# stromplatine.net
KiCad netlist of a schematic drawn in EAGLE
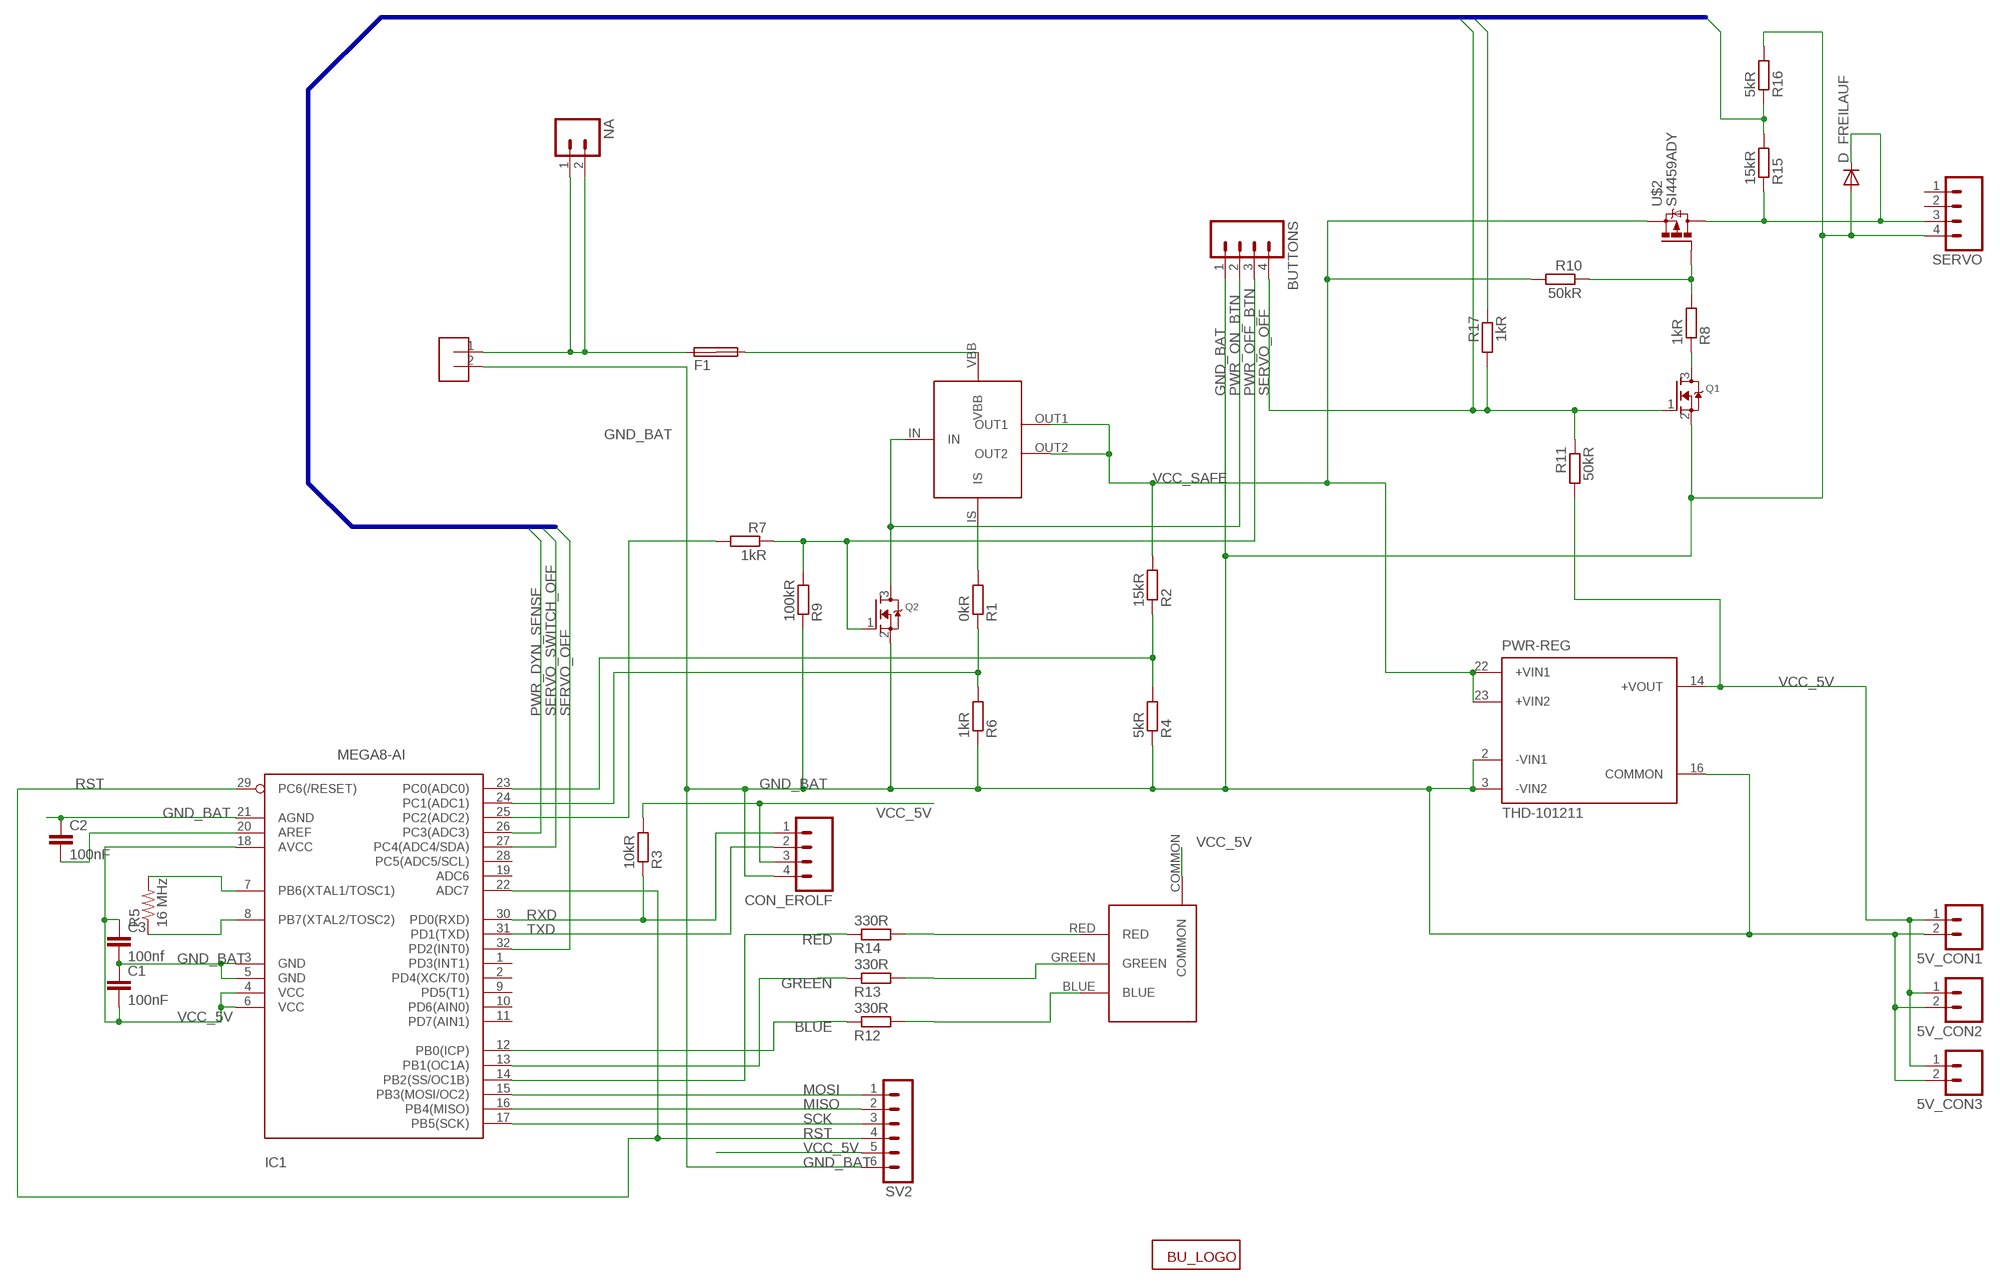
[diagram p0: schematic, sheet 1]

(export (version "E")
  (design (tool "Eeschema 10.0.6"))
  (components
    (comp (ref "5V_CON1")
      (value "M02")
      (footprint "eagle-import:02P")
      (libsource (lib "eagle-import") (part "M02"))
    )
    (comp (ref "5V_CON2")
      (value "M02")
      (footprint "eagle-import:02P")
      (libsource (lib "eagle-import") (part "M02"))
    )
    (comp (ref "5V_CON3")
      (value "M02")
      (footprint "eagle-import:02P")
      (libsource (lib "eagle-import") (part "M02"))
    )
    (comp (ref "BUTTONS")
      (value "M04")
      (footprint "eagle-import:04P")
      (fields (field (name "OC_FARNELL") "unknown") (field (name "OC_NEWARK") "unknown"))
      (libsource (lib "eagle-import") (part "M04"))
    )
    (comp (ref "C1")
      (value "100nF")
      (footprint "eagle-import:C0805")
      (libsource (lib "eagle-import") (part "C-EUC0805"))
    )
    (comp (ref "C2")
      (value "100nF")
      (footprint "eagle-import:C0805")
      (libsource (lib "eagle-import") (part "C-EUC0805"))
    )
    (comp (ref "C3")
      (value "100nf")
      (footprint "eagle-import:C0805")
      (libsource (lib "eagle-import") (part "C-EUC0805"))
    )
    (comp (ref "CON_BAT")
      (value "STROMSTECKER")
      (footprint "eagle-import:STROMSTECKER")
      (libsource (lib "eagle-import") (part "STROMSTECKER"))
    )
    (comp (ref "CON_EROLF")
      (value "M04")
      (footprint "eagle-import:04P")
      (fields (field (name "OC_FARNELL") "unknown") (field (name "OC_NEWARK") "unknown"))
      (libsource (lib "eagle-import") (part "M04"))
    )
    (comp (ref "D_FREILAUF")
      (value "DIODE-DO-214AC")
      (footprint "eagle-import:DO-214AC")
      (libsource (lib "eagle-import") (part "DIODE-DO-214AC"))
    )
    (comp (ref "F1")
      (value "SHK20Q")
      (footprint "eagle-import:SHK20Q")
      (libsource (lib "eagle-import") (part "SHK20Q"))
    )
    (comp (ref "IC1")
      (value "MEGA8-AI")
      (footprint "eagle-import:TQFP32-08")
      (libsource (lib "eagle-import") (part "MEGA8-AI"))
    )
    (comp (ref "NA")
      (value "M02")
      (footprint "eagle-import:02P")
      (fields (field (name "OC_FARNELL") "unknown") (field (name "OC_NEWARK") "unknown"))
      (libsource (lib "eagle-import") (part "M02"))
    )
    (comp (ref "PWR-REG")
      (value "THD-101211")
      (footprint "eagle-import:TEN3XXXX")
      (libsource (lib "eagle-import") (part "TEN_30512"))
    )
    (comp (ref "Q1")
      (value "MOSFET-NREFLOW")
      (footprint "eagle-import:SOT23")
      (libsource (lib "eagle-import") (part "MOSFET-NREFLOW"))
    )
    (comp (ref "Q2")
      (value "MOSFET-NREFLOW")
      (footprint "eagle-import:SOT23")
      (libsource (lib "eagle-import") (part "MOSFET-NREFLOW"))
    )
    (comp (ref "R1")
      (value "0kR")
      (footprint "eagle-import:M0805")
      (libsource (lib "eagle-import") (part "R-EU_M0805"))
    )
    (comp (ref "R2")
      (value "15kR")
      (footprint "eagle-import:M0805")
      (libsource (lib "eagle-import") (part "R-EU_M0805"))
    )
    (comp (ref "R3")
      (value "10kR")
      (footprint "eagle-import:M0805")
      (libsource (lib "eagle-import") (part "R-EU_M0805"))
    )
    (comp (ref "R4")
      (value "5kR")
      (footprint "eagle-import:M0805")
      (libsource (lib "eagle-import") (part "R-EU_M0805"))
    )
    (comp (ref "R5")
      (value "16 MHz")
      (footprint "eagle-import:MINI_MELF-0102W")
      (libsource (lib "eagle-import") (part "R-US_MELF0102W"))
    )
    (comp (ref "R6")
      (value "1kR")
      (footprint "eagle-import:M0805")
      (libsource (lib "eagle-import") (part "R-EU_M0805"))
    )
    (comp (ref "R7")
      (value "1kR")
      (footprint "eagle-import:M0805")
      (libsource (lib "eagle-import") (part "R-EU_M0805"))
    )
    (comp (ref "R8")
      (value "1kR")
      (footprint "eagle-import:M0805")
      (libsource (lib "eagle-import") (part "R-EU_M0805"))
    )
    (comp (ref "R9")
      (value "100kR")
      (footprint "eagle-import:M0805")
      (libsource (lib "eagle-import") (part "R-EU_M0805"))
    )
    (comp (ref "R10")
      (value "50kR")
      (footprint "eagle-import:M0805")
      (libsource (lib "eagle-import") (part "R-EU_M0805"))
    )
    (comp (ref "R11")
      (value "50kR")
      (footprint "eagle-import:M0805")
      (libsource (lib "eagle-import") (part "R-EU_M0805"))
    )
    (comp (ref "R12")
      (value "330R")
      (footprint "eagle-import:M0805")
      (libsource (lib "eagle-import") (part "R-EU_M0805"))
    )
    (comp (ref "R13")
      (value "330R")
      (footprint "eagle-import:M0805")
      (libsource (lib "eagle-import") (part "R-EU_M0805"))
    )
    (comp (ref "R14")
      (value "330R")
      (footprint "eagle-import:M0805")
      (libsource (lib "eagle-import") (part "R-EU_M0805"))
    )
    (comp (ref "R15")
      (value "15kR")
      (footprint "eagle-import:M0805")
      (libsource (lib "eagle-import") (part "R-EU_M0805"))
    )
    (comp (ref "R16")
      (value "5kR")
      (footprint "eagle-import:M0805")
      (libsource (lib "eagle-import") (part "R-EU_M0805"))
    )
    (comp (ref "R17")
      (value "1kR")
      (footprint "eagle-import:M0805")
      (libsource (lib "eagle-import") (part "R-EU_M0805"))
    )
    (comp (ref "SERVO")
      (value "M04")
      (footprint "eagle-import:04P")
      (libsource (lib "eagle-import") (part "M04"))
    )
    (comp (ref "SV2")
      (value "MA06-1")
      (footprint "eagle-import:MA06-1")
      (libsource (lib "eagle-import") (part "MA06-1"))
    )
    (comp (ref "U$1")
      (value "BTS555")
      (footprint "eagle-import:PG-TO218")
      (libsource (lib "eagle-import") (part "BTS555"))
    )
    (comp (ref "U$2")
      (value "SI4459ADY")
      (footprint "eagle-import:SO-8")
      (libsource (lib "eagle-import") (part "SI4459ADY"))
    )
    (comp (ref "U$3")
      (value "RGB-LED")
      (footprint "eagle-import:4-PLCC")
      (libsource (lib "eagle-import") (part "RGB-LED"))
    )
    (comp (ref "U$4")
      (value "LOGO")
      (footprint "eagle-import:LOGO")
      (libsource (lib "eagle-import") (part "LOGO"))
    )
  )
  (nets
    (net (code "1") (name "/BLUE") (class "Default")
      (node (ref "IC1") (pin "12") (pinfunction "PB0(ICP)_12") (pintype "bidirectional"))
      (node (ref "R12") (pin "1") (pinfunction "1_1") (pintype "passive"))
    )
    (net (code "2") (name "/GND_BAT") (class "Default")
      (node (ref "5V_CON1") (pin "2") (pinfunction "2_2") (pintype "passive"))
      (node (ref "5V_CON2") (pin "2") (pinfunction "2_2") (pintype "passive"))
      (node (ref "5V_CON3") (pin "2") (pinfunction "2_2") (pintype "passive"))
      (node (ref "BUTTONS") (pin "1") (pinfunction "1_1") (pintype "passive"))
      (node (ref "C1") (pin "1") (pinfunction "1_1") (pintype "passive"))
      (node (ref "C2") (pin "1") (pinfunction "1_1") (pintype "passive"))
      (node (ref "C3") (pin "2") (pinfunction "2_2") (pintype "passive"))
      (node (ref "CON_BAT") (pin "2") (pinfunction "2_2") (pintype "bidirectional"))
      (node (ref "CON_EROLF") (pin "4") (pinfunction "4_4") (pintype "passive"))
      (node (ref "D_FREILAUF") (pin "A") (pinfunction "A_A") (pintype "passive"))
      (node (ref "IC1") (pin "21") (pinfunction "AGND_21") (pintype "bidirectional"))
      (node (ref "IC1") (pin "3") (pinfunction "GND_3") (pintype "bidirectional"))
      (node (ref "IC1") (pin "5") (pinfunction "GND_5") (pintype "bidirectional"))
      (node (ref "PWR-REG") (pin "16") (pinfunction "COMMON_16") (pintype "passive"))
      (node (ref "PWR-REG") (pin "2") (pinfunction "-VIN1_2") (pintype "input"))
      (node (ref "PWR-REG") (pin "3") (pinfunction "-VIN2_3") (pintype "input"))
      (node (ref "Q1") (pin "2") (pinfunction "S_2") (pintype "bidirectional"))
      (node (ref "Q2") (pin "2") (pinfunction "S_2") (pintype "bidirectional"))
      (node (ref "R16") (pin "2") (pinfunction "2_2") (pintype "passive"))
      (node (ref "R4") (pin "1") (pinfunction "1_1") (pintype "passive"))
      (node (ref "R6") (pin "1") (pinfunction "1_1") (pintype "passive"))
      (node (ref "R9") (pin "1") (pinfunction "1_1") (pintype "passive"))
      (node (ref "SERVO") (pin "4") (pinfunction "4_4") (pintype "passive"))
      (node (ref "SV2") (pin "6") (pinfunction "6_6") (pintype "passive"))
    )
    (net (code "3") (name "/GREEN") (class "Default")
      (node (ref "IC1") (pin "13") (pinfunction "PB1(OC1A)_13") (pintype "bidirectional"))
      (node (ref "R13") (pin "1") (pinfunction "1_1") (pintype "passive"))
    )
    (net (code "4") (name "/MISO") (class "Default")
      (node (ref "IC1") (pin "16") (pinfunction "PB4(MISO)_16") (pintype "bidirectional"))
      (node (ref "SV2") (pin "2") (pinfunction "2_2") (pintype "passive"))
    )
    (net (code "5") (name "/MOSI") (class "Default")
      (node (ref "IC1") (pin "15") (pinfunction "PB3(MOSI/OC2)_15") (pintype "bidirectional"))
      (node (ref "SV2") (pin "1") (pinfunction "1_1") (pintype "passive"))
    )
    (net (code "6") (name "/PWR_DYN_SENSE") (class "Default")
      (node (ref "IC1") (pin "26") (pinfunction "PC3(ADC3)_26") (pintype "bidirectional"))
      (node (ref "R15") (pin "2") (pinfunction "2_2") (pintype "passive"))
      (node (ref "R16") (pin "1") (pinfunction "1_1") (pintype "passive"))
    )
    (net (code "7") (name "/PWR_OFF_BTN") (class "Default")
      (node (ref "BUTTONS") (pin "3") (pinfunction "3_3") (pintype "passive"))
      (node (ref "Q2") (pin "1") (pinfunction "G_1") (pintype "bidirectional"))
      (node (ref "R7") (pin "1") (pinfunction "1_1") (pintype "passive"))
      (node (ref "R9") (pin "2") (pinfunction "2_2") (pintype "passive"))
    )
    (net (code "8") (name "/PWR_ON_BTN") (class "Default")
      (node (ref "BUTTONS") (pin "2") (pinfunction "2_2") (pintype "passive"))
      (node (ref "Q2") (pin "3") (pinfunction "D_3") (pintype "bidirectional"))
      (node (ref "U$1") (pin "IN") (pinfunction "IN_IN") (pintype "bidirectional"))
    )
    (net (code "9") (name "/RED") (class "Default")
      (node (ref "IC1") (pin "14") (pinfunction "PB2(SS/OC1B)_14") (pintype "bidirectional"))
      (node (ref "R14") (pin "1") (pinfunction "1_1") (pintype "passive"))
    )
    (net (code "10") (name "/RST") (class "Default")
      (node (ref "IC1") (pin "22") (pinfunction "ADC7_22") (pintype "bidirectional"))
      (node (ref "IC1") (pin "29") (pinfunction "PC6(/RESET)_29") (pintype "bidirectional"))
      (node (ref "SV2") (pin "4") (pinfunction "4_4") (pintype "passive"))
    )
    (net (code "11") (name "/RXD") (class "Default")
      (node (ref "CON_EROLF") (pin "1") (pinfunction "1_1") (pintype "passive"))
      (node (ref "IC1") (pin "30") (pinfunction "PD0(RXD)_30") (pintype "bidirectional"))
      (node (ref "R3") (pin "1") (pinfunction "1_1") (pintype "passive"))
    )
    (net (code "12") (name "/SCK") (class "Default")
      (node (ref "IC1") (pin "17") (pinfunction "PB5(SCK)_17") (pintype "bidirectional"))
      (node (ref "SV2") (pin "3") (pinfunction "3_3") (pintype "passive"))
    )
    (net (code "13") (name "/SERVO_OFF") (class "Default")
      (node (ref "BUTTONS") (pin "4") (pinfunction "4_4") (pintype "passive"))
      (node (ref "IC1") (pin "32") (pinfunction "PD2(INT0)_32") (pintype "bidirectional"))
      (node (ref "Q1") (pin "1") (pinfunction "G_1") (pintype "bidirectional"))
      (node (ref "R11") (pin "1") (pinfunction "1_1") (pintype "passive"))
      (node (ref "R17") (pin "2") (pinfunction "2_2") (pintype "passive"))
    )
    (net (code "14") (name "/SERVO_SWITCH_OFF") (class "Default")
      (node (ref "IC1") (pin "27") (pinfunction "PC4(ADC4/SDA)_27") (pintype "bidirectional"))
      (node (ref "R17") (pin "1") (pinfunction "1_1") (pintype "passive"))
    )
    (net (code "15") (name "/TXD") (class "Default")
      (node (ref "CON_EROLF") (pin "2") (pinfunction "2_2") (pintype "passive"))
      (node (ref "IC1") (pin "31") (pinfunction "PD1(TXD)_31") (pintype "bidirectional"))
    )
    (net (code "16") (name "/VCC_5V") (class "Default")
      (node (ref "5V_CON1") (pin "1") (pinfunction "1_1") (pintype "passive"))
      (node (ref "5V_CON2") (pin "1") (pinfunction "1_1") (pintype "passive"))
      (node (ref "5V_CON3") (pin "1") (pinfunction "1_1") (pintype "passive"))
      (node (ref "C1") (pin "2") (pinfunction "2_2") (pintype "passive"))
      (node (ref "C3") (pin "1") (pinfunction "1_1") (pintype "passive"))
      (node (ref "CON_EROLF") (pin "3") (pinfunction "3_3") (pintype "passive"))
      (node (ref "IC1") (pin "18") (pinfunction "AVCC_18") (pintype "bidirectional"))
      (node (ref "IC1") (pin "4") (pinfunction "VCC_4") (pintype "bidirectional"))
      (node (ref "IC1") (pin "6") (pinfunction "VCC_6") (pintype "bidirectional"))
      (node (ref "PWR-REG") (pin "14") (pinfunction "+VOUT_14") (pintype "passive"))
      (node (ref "R11") (pin "2") (pinfunction "2_2") (pintype "passive"))
      (node (ref "R3") (pin "2") (pinfunction "2_2") (pintype "passive"))
      (node (ref "SV2") (pin "5") (pinfunction "5_5") (pintype "passive"))
      (node (ref "U$3") (pin "COMMON") (pinfunction "COMMON_COMMON") (pintype "bidirectional"))
    )
    (net (code "17") (name "/VCC_SAFE") (class "Default")
      (node (ref "PWR-REG") (pin "22") (pinfunction "+VIN1_22") (pintype "input"))
      (node (ref "PWR-REG") (pin "23") (pinfunction "+VIN2_23") (pintype "input"))
      (node (ref "R10") (pin "2") (pinfunction "2_2") (pintype "passive"))
      (node (ref "R2") (pin "2") (pinfunction "2_2") (pintype "passive"))
      (node (ref "U$1") (pin "OUT1") (pinfunction "OUT1_OUT1") (pintype "bidirectional"))
      (node (ref "U$1") (pin "OUT2") (pinfunction "OUT2_OUT2") (pintype "bidirectional"))
      (node (ref "U$2") (pin "P1") (pinfunction "S_P1") (pintype "passive"))
      (node (ref "U$2") (pin "P2") (pinfunction "S_P2") (pintype "passive"))
      (node (ref "U$2") (pin "P3") (pinfunction "S_P3") (pintype "passive"))
    )
    (net (code "18") (name "Net-(CON_BAT-Pad1)") (class "Default")
      (node (ref "CON_BAT") (pin "1") (pinfunction "1_1") (pintype "bidirectional"))
      (node (ref "F1") (pin "1A") (pinfunction "1A_1A") (pintype "passive"))
      (node (ref "NA") (pin "1") (pinfunction "1_1") (pintype "passive"))
      (node (ref "NA") (pin "2") (pinfunction "2_2") (pintype "passive"))
    )
    (net (code "19") (name "Net-(D_FREILAUF-PadC)") (class "Default")
      (node (ref "D_FREILAUF") (pin "C") (pinfunction "C_C") (pintype "passive"))
      (node (ref "R15") (pin "1") (pinfunction "1_1") (pintype "passive"))
      (node (ref "SERVO") (pin "3") (pinfunction "3_3") (pintype "passive"))
      (node (ref "U$2") (pin "P5") (pinfunction "D_P5") (pintype "passive"))
      (node (ref "U$2") (pin "P6") (pinfunction "D_P6") (pintype "passive"))
      (node (ref "U$2") (pin "P7") (pinfunction "D_P7") (pintype "passive"))
      (node (ref "U$2") (pin "P8") (pinfunction "D_P8") (pintype "passive"))
    )
    (net (code "20") (name "Net-(F1-Pad2A)") (class "Default")
      (node (ref "F1") (pin "2A") (pinfunction "2A_2A") (pintype "passive"))
      (node (ref "U$1") (pin "VBB") (pinfunction "VBB_VBB") (pintype "bidirectional"))
    )
    (net (code "21") (name "Net-(IC1-AREF)") (class "Default")
      (node (ref "C2") (pin "2") (pinfunction "2_2") (pintype "passive"))
      (node (ref "IC1") (pin "20") (pinfunction "AREF_20") (pintype "bidirectional"))
    )
    (net (code "22") (name "Net-(IC1-PB6(XTAL1{slash}TOSC1))") (class "Default")
      (node (ref "IC1") (pin "7") (pinfunction "PB6(XTAL1/TOSC1)_7") (pintype "bidirectional"))
      (node (ref "R5") (pin "2") (pinfunction "2_2") (pintype "passive"))
    )
    (net (code "23") (name "Net-(IC1-PB7(XTAL2{slash}TOSC2))") (class "Default")
      (node (ref "IC1") (pin "8") (pinfunction "PB7(XTAL2/TOSC2)_8") (pintype "bidirectional"))
      (node (ref "R5") (pin "1") (pinfunction "1_1") (pintype "passive"))
    )
    (net (code "24") (name "Net-(IC1-PC0(ADC0))") (class "Default")
      (node (ref "IC1") (pin "23") (pinfunction "PC0(ADC0)_23") (pintype "bidirectional"))
      (node (ref "R2") (pin "1") (pinfunction "1_1") (pintype "passive"))
      (node (ref "R4") (pin "2") (pinfunction "2_2") (pintype "passive"))
    )
    (net (code "25") (name "Net-(IC1-PC1(ADC1))") (class "Default")
      (node (ref "IC1") (pin "24") (pinfunction "PC1(ADC1)_24") (pintype "bidirectional"))
      (node (ref "R1") (pin "1") (pinfunction "1_1") (pintype "passive"))
      (node (ref "R6") (pin "2") (pinfunction "2_2") (pintype "passive"))
    )
    (net (code "26") (name "Net-(IC1-PC2(ADC2))") (class "Default")
      (node (ref "IC1") (pin "25") (pinfunction "PC2(ADC2)_25") (pintype "bidirectional"))
      (node (ref "R7") (pin "2") (pinfunction "2_2") (pintype "passive"))
    )
    (net (code "27") (name "Net-(Q1-D)") (class "Default")
      (node (ref "Q1") (pin "3") (pinfunction "D_3") (pintype "bidirectional"))
      (node (ref "R8") (pin "1") (pinfunction "1_1") (pintype "passive"))
    )
    (net (code "28") (name "Net-(R1-Pad2)") (class "Default")
      (node (ref "R1") (pin "2") (pinfunction "2_2") (pintype "passive"))
      (node (ref "U$1") (pin "IS") (pinfunction "IS_IS") (pintype "bidirectional"))
    )
    (net (code "29") (name "Net-(R12-Pad2)") (class "Default")
      (node (ref "R12") (pin "2") (pinfunction "2_2") (pintype "passive"))
      (node (ref "U$3") (pin "BLUE") (pinfunction "BLUE_BLUE") (pintype "bidirectional"))
    )
    (net (code "30") (name "Net-(R13-Pad2)") (class "Default")
      (node (ref "R13") (pin "2") (pinfunction "2_2") (pintype "passive"))
      (node (ref "U$3") (pin "GREEN") (pinfunction "GREEN_GREEN") (pintype "bidirectional"))
    )
    (net (code "31") (name "Net-(R14-Pad2)") (class "Default")
      (node (ref "R14") (pin "2") (pinfunction "2_2") (pintype "passive"))
      (node (ref "U$3") (pin "RED") (pinfunction "RED_RED") (pintype "bidirectional"))
    )
    (net (code "32") (name "Net-(U$2-G)") (class "Default")
      (node (ref "R10") (pin "1") (pinfunction "1_1") (pintype "passive"))
      (node (ref "R8") (pin "2") (pinfunction "2_2") (pintype "passive"))
      (node (ref "U$2") (pin "P4") (pinfunction "G_P4") (pintype "passive"))
    )
    (net (code "33") (name "unconnected-(F1-Pad1B)") (class "Default")
      (node (ref "F1") (pin "1B") (pinfunction "1B_1B") (pintype "passive"))
    )
    (net (code "34") (name "unconnected-(F1-Pad2B)") (class "Default")
      (node (ref "F1") (pin "2B") (pinfunction "2B_2B") (pintype "passive"))
    )
    (net (code "35") (name "unconnected-(IC1-ADC6-Pad19)") (class "Default")
      (node (ref "IC1") (pin "19") (pinfunction "ADC6_19") (pintype "bidirectional"))
    )
    (net (code "36") (name "unconnected-(IC1-PC5(ADC5{slash}SCL)-Pad28)") (class "Default")
      (node (ref "IC1") (pin "28") (pinfunction "PC5(ADC5/SCL)_28") (pintype "bidirectional"))
    )
    (net (code "37") (name "unconnected-(IC1-PD3(INT1)-Pad1)") (class "Default")
      (node (ref "IC1") (pin "1") (pinfunction "PD3(INT1)_1") (pintype "bidirectional"))
    )
    (net (code "38") (name "unconnected-(IC1-PD4(XCK{slash}T0)-Pad2)") (class "Default")
      (node (ref "IC1") (pin "2") (pinfunction "PD4(XCK/T0)_2") (pintype "bidirectional"))
    )
    (net (code "39") (name "unconnected-(IC1-PD5(T1)-Pad9)") (class "Default")
      (node (ref "IC1") (pin "9") (pinfunction "PD5(T1)_9") (pintype "bidirectional"))
    )
    (net (code "40") (name "unconnected-(IC1-PD6(AIN0)-Pad10)") (class "Default")
      (node (ref "IC1") (pin "10") (pinfunction "PD6(AIN0)_10") (pintype "bidirectional"))
    )
    (net (code "41") (name "unconnected-(IC1-PD7(AIN1)-Pad11)") (class "Default")
      (node (ref "IC1") (pin "11") (pinfunction "PD7(AIN1)_11") (pintype "bidirectional"))
    )
    (net (code "42") (name "unconnected-(SERVO-Pad1)") (class "Default")
      (node (ref "SERVO") (pin "1") (pinfunction "1_1") (pintype "passive"))
    )
    (net (code "43") (name "unconnected-(SERVO-Pad2)") (class "Default")
      (node (ref "SERVO") (pin "2") (pinfunction "2_2") (pintype "passive"))
    )
  )
)
